# TC364_MainBoard_Power_V1_3.net
KiCad netlist of a schematic drawn in Altium Designer
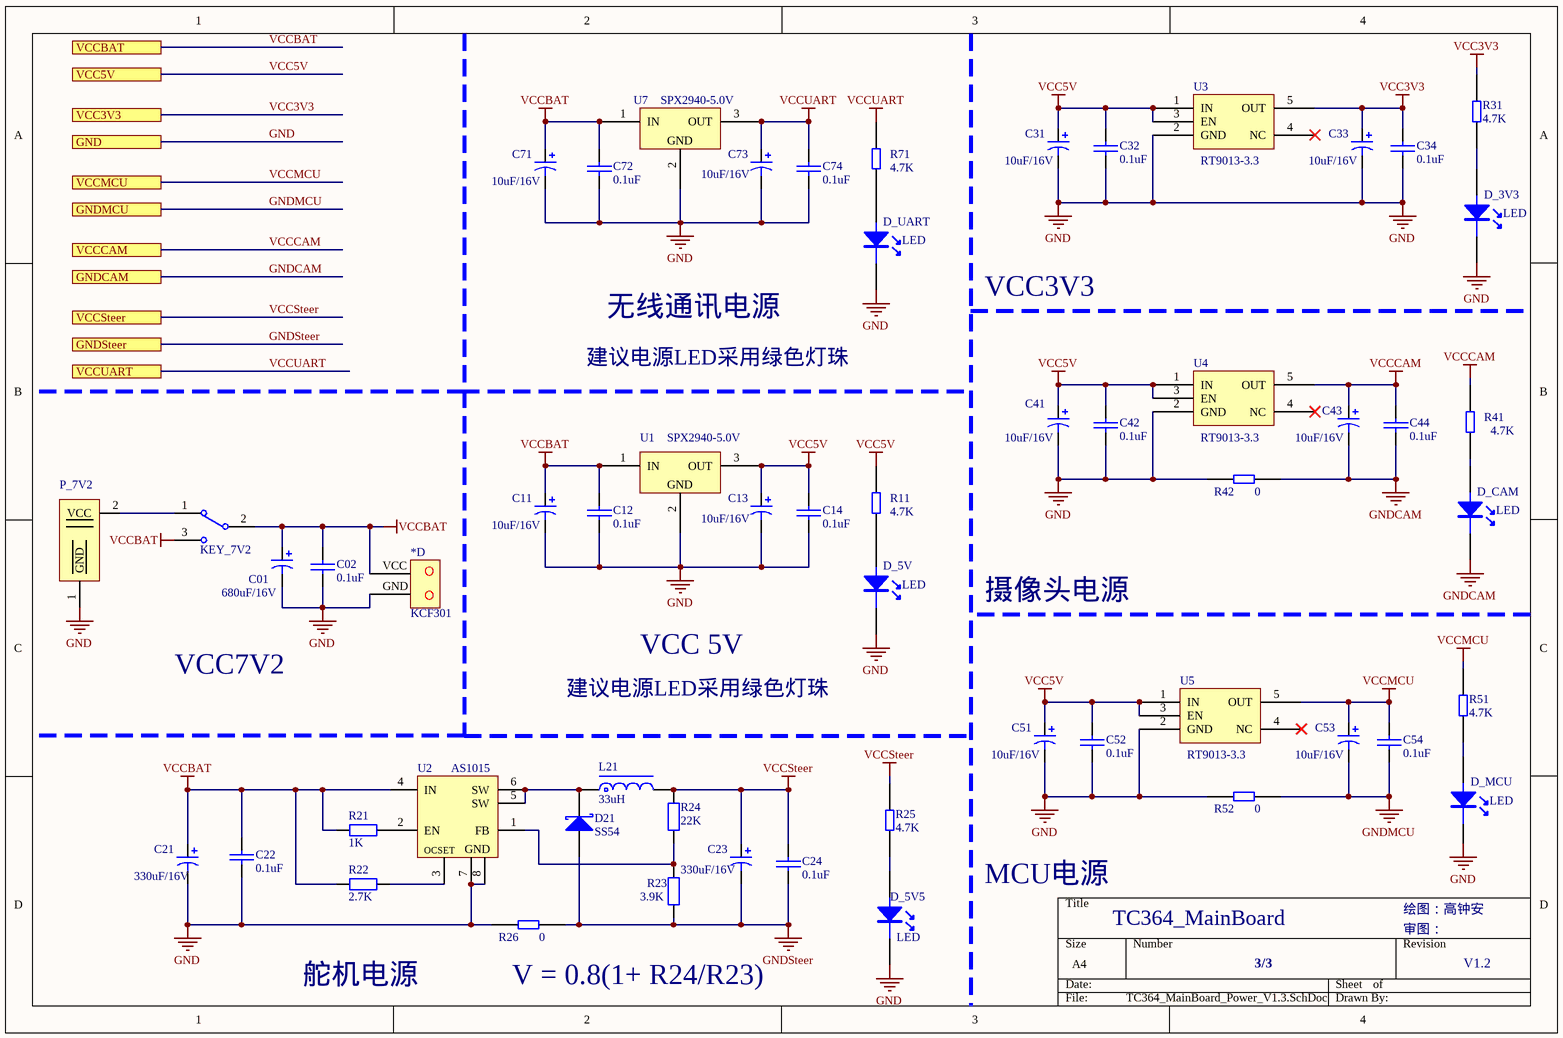
[diagram p0: TC364_MainBoard_Power_V1.3.SchDoc]

(export (version "E")
  (design (tool "Eeschema 10.0.6"))
  (components
    (comp (ref "*") (value "KCF301") (footprint "KF301-2P") (libsource (lib "BaseLib_SCH") (part "KCF301")))
    (comp (ref "C01")
      (value "680uF/16V")
      (footprint "CAP 3.5*8*11.5 - GD")
      (description "Polarized Capacitor (Radial)")
      (fields (field (name "PUBLISHER") "Altium Limited"))
      (libsource (lib "Miscellaneous Devices") (part "Cap Pol1"))
    )
    (comp (ref "C02")
      (value "0.1uF")
      (footprint "0805C")
      (description "Capacitor")
      (libsource (lib "Protel99Lib_SCH") (part "CAP"))
    )
    (comp (ref "C11")
      (value "10uF/16V")
      (footprint "CASE-A_3216")
      (description "Polarized Capacitor (Radial)")
      (fields (field (name "PUBLISHER") "Altium Limited"))
      (libsource (lib "Miscellaneous Devices") (part "Cap Pol1"))
    )
    (comp (ref "C12")
      (value "0.1uF")
      (footprint "0805C")
      (description "Capacitor")
      (libsource (lib "Protel99Lib_SCH") (part "CAP"))
    )
    (comp (ref "C13")
      (value "10uF/16V")
      (footprint "CASE-A_3216")
      (description "Polarized Capacitor (Radial)")
      (fields (field (name "PUBLISHER") "Altium Limited"))
      (libsource (lib "Miscellaneous Devices") (part "Cap Pol1"))
    )
    (comp (ref "C14")
      (value "0.1uF")
      (footprint "0805C")
      (description "Capacitor")
      (libsource (lib "Protel99Lib_SCH") (part "CAP"))
    )
    (comp (ref "C21")
      (value "330uF/16V")
      (footprint "CAP 2.5*6.3*11.2 - BK")
      (description "Polarized Capacitor (Radial)")
      (fields (field (name "PUBLISHER") "Altium Limited"))
      (libsource (lib "Miscellaneous Devices") (part "Cap Pol1"))
    )
    (comp (ref "C22")
      (value "0.1uF")
      (footprint "0805C")
      (description "Capacitor")
      (libsource (lib "Protel99Lib_SCH") (part "CAP"))
    )
    (comp (ref "C23")
      (value "330uF/16V")
      (footprint "CAP 2.5*6.3*11.2 - BK")
      (description "Polarized Capacitor (Radial)")
      (fields (field (name "PUBLISHER") "Altium Limited"))
      (libsource (lib "Miscellaneous Devices") (part "Cap Pol1"))
    )
    (comp (ref "C24")
      (value "0.1uF")
      (footprint "0805C")
      (description "Capacitor")
      (libsource (lib "Protel99Lib_SCH") (part "CAP"))
    )
    (comp (ref "C31")
      (value "10uF/16V")
      (footprint "CASE-A_3216")
      (description "Polarized Capacitor (Radial)")
      (fields (field (name "PUBLISHER") "Altium Limited"))
      (libsource (lib "Miscellaneous Devices") (part "Cap Pol1"))
    )
    (comp (ref "C32")
      (value "0.1uF")
      (footprint "0805C")
      (description "Capacitor")
      (libsource (lib "Protel99Lib_SCH") (part "CAP"))
    )
    (comp (ref "C33")
      (value "10uF/16V")
      (footprint "CASE-A_3216")
      (description "Polarized Capacitor (Radial)")
      (fields (field (name "PUBLISHER") "Altium Limited"))
      (libsource (lib "Miscellaneous Devices") (part "Cap Pol1"))
    )
    (comp (ref "C34")
      (value "0.1uF")
      (footprint "0805C")
      (description "Capacitor")
      (libsource (lib "Protel99Lib_SCH") (part "CAP"))
    )
    (comp (ref "C41")
      (value "10uF/16V")
      (footprint "CASE-A_3216")
      (description "Polarized Capacitor (Radial)")
      (fields (field (name "PUBLISHER") "Altium Limited"))
      (libsource (lib "Miscellaneous Devices") (part "Cap Pol1"))
    )
    (comp (ref "C42")
      (value "0.1uF")
      (footprint "0805C")
      (description "Capacitor")
      (libsource (lib "Protel99Lib_SCH") (part "CAP"))
    )
    (comp (ref "C43")
      (value "10uF/16V")
      (footprint "CASE-A_3216")
      (description "Polarized Capacitor (Radial)")
      (fields (field (name "PUBLISHER") "Altium Limited"))
      (libsource (lib "Miscellaneous Devices") (part "Cap Pol1"))
    )
    (comp (ref "C44")
      (value "0.1uF")
      (footprint "0805C")
      (description "Capacitor")
      (libsource (lib "Protel99Lib_SCH") (part "CAP"))
    )
    (comp (ref "C51")
      (value "10uF/16V")
      (footprint "CASE-A_3216")
      (description "Polarized Capacitor (Radial)")
      (fields (field (name "PUBLISHER") "Altium Limited"))
      (libsource (lib "Miscellaneous Devices") (part "Cap Pol1"))
    )
    (comp (ref "C52")
      (value "0.1uF")
      (footprint "0805C")
      (description "Capacitor")
      (libsource (lib "Protel99Lib_SCH") (part "CAP"))
    )
    (comp (ref "C53")
      (value "10uF/16V")
      (footprint "CASE-A_3216")
      (description "Polarized Capacitor (Radial)")
      (fields (field (name "PUBLISHER") "Altium Limited"))
      (libsource (lib "Miscellaneous Devices") (part "Cap Pol1"))
    )
    (comp (ref "C54")
      (value "0.1uF")
      (footprint "0805C")
      (description "Capacitor")
      (libsource (lib "Protel99Lib_SCH") (part "CAP"))
    )
    (comp (ref "C71")
      (value "10uF/16V")
      (footprint "CASE-A_3216")
      (description "Polarized Capacitor (Radial)")
      (fields (field (name "PUBLISHER") "Altium Limited"))
      (libsource (lib "Miscellaneous Devices") (part "Cap Pol1"))
    )
    (comp (ref "C72")
      (value "0.1uF")
      (footprint "0805C")
      (description "Capacitor")
      (libsource (lib "Protel99Lib_SCH") (part "CAP"))
    )
    (comp (ref "C73")
      (value "10uF/16V")
      (footprint "CASE-A_3216")
      (description "Polarized Capacitor (Radial)")
      (fields (field (name "PUBLISHER") "Altium Limited"))
      (libsource (lib "Miscellaneous Devices") (part "Cap Pol1"))
    )
    (comp (ref "C74")
      (value "0.1uF")
      (footprint "0805C")
      (description "Capacitor")
      (libsource (lib "Protel99Lib_SCH") (part "CAP"))
    )
    (comp (ref "D21")
      (value "SS54")
      (footprint "SMA")
      (description "肖特基二极管")
      (libsource (lib "0.2 -  二极管-整流桥") (part "SS34"))
    )
    (comp (ref "D_3V3")
      (value "LED")
      (footprint "0805_LED_S1")
      (description "发光二极管")
      (libsource (lib "jianing") (part "LED"))
    )
    (comp (ref "D_5V")
      (value "LED")
      (footprint "0805_LED_S1")
      (description "发光二极管")
      (libsource (lib "jianing") (part "LED"))
    )
    (comp (ref "D_5V5")
      (value "LED")
      (footprint "0805_LED_S1")
      (description "发光二极管")
      (libsource (lib "jianing") (part "LED"))
    )
    (comp (ref "D_CAM")
      (value "LED")
      (footprint "0805_LED_S1")
      (description "发光二极管")
      (libsource (lib "jianing") (part "LED"))
    )
    (comp (ref "D_MCU")
      (value "LED")
      (footprint "0805_LED_S1")
      (description "发光二极管")
      (libsource (lib "jianing") (part "LED"))
    )
    (comp (ref "D_UART")
      (value "LED")
      (footprint "0805_LED_S1")
      (description "发光二极管")
      (libsource (lib "jianing") (part "LED"))
    )
    (comp (ref "KEY_7V2")
      (value "SS-12F23")
      (footprint "KEY_7V2")
      (description "1路波动开关")
      (fields (field (name "版权归属") "封装库来自淘宝 ID：黄晶宝石"))
      (libsource (lib "0.7 - 常用按键-开关") (part "SSW-1P"))
    )
    (comp (ref "L21")
      (value "33uH")
      (footprint "7*7 L")
      (description "功率屏蔽电感")
      (fields (field (name "版权归属") "封装库来自淘宝 ID：黄晶宝石"))
      (libsource (lib "0.1 - 电阻-电容-电感") (part "L-CDRH"))
    )
    (comp (ref "P_7V2")
      (value "T_Type_Adapter")
      (footprint "T_Type_Adapter")
      (libsource (lib "Schlib1") (part "T_Type_Adapter"))
    )
    (comp (ref "R11") (value "4.7K") (footprint "0805R") (libsource (lib "BaseLib_SCH") (part "RES")))
    (comp (ref "R21")
      (value "1K")
      (footprint "0805R")
      (description "贴片电阻")
      (fields (field (name "版权归属") "源创客"))
      (libsource (lib "jianing") (part "RES"))
    )
    (comp (ref "R22")
      (value "2.7K")
      (footprint "0805R")
      (description "贴片电阻")
      (fields (field (name "版权归属") "源创客"))
      (libsource (lib "jianing") (part "RES"))
    )
    (comp (ref "R23")
      (value "3.9K")
      (footprint "0805R")
      (description "贴片电阻")
      (fields (field (name "版权归属") "源创客"))
      (libsource (lib "jianing") (part "RES"))
    )
    (comp (ref "R24")
      (value "22K")
      (footprint "0805R")
      (description "贴片电阻")
      (fields (field (name "版权归属") "源创客"))
      (libsource (lib "jianing") (part "RES"))
    )
    (comp (ref "R25") (value "4.7K") (footprint "0805R") (libsource (lib "BaseLib_SCH") (part "RES")))
    (comp (ref "R26") (value "0") (footprint "0805R") (libsource (lib "BaseLib_SCH") (part "RES")))
    (comp (ref "R31") (value "4.7K") (footprint "0805R") (libsource (lib "BaseLib_SCH") (part "RES")))
    (comp (ref "R41") (value "4.7K") (footprint "0805R") (libsource (lib "BaseLib_SCH") (part "RES")))
    (comp (ref "R42") (value "0") (footprint "0805R") (libsource (lib "BaseLib_SCH") (part "RES")))
    (comp (ref "R51") (value "4.7K") (footprint "0805R") (libsource (lib "BaseLib_SCH") (part "RES")))
    (comp (ref "R52") (value "0") (footprint "0805R") (libsource (lib "BaseLib_SCH") (part "RES")))
    (comp (ref "R71") (value "4.7K") (footprint "0805R") (libsource (lib "BaseLib_SCH") (part "RES")))
    (comp (ref "U1")
      (value "SPX2940-5.0V")
      (footprint "TO-220(TO-220-3)")
      (description "5V稳压芯片")
      (fields (field (name "版权归属") "封装库来自淘宝 ID：黄晶宝石"))
      (libsource (lib "1.1 - 电源类芯片") (part "LM2940"))
    )
    (comp (ref "U2")
      (value "AS1015")
      (footprint "SOP-8_150mil")
      (description "可调升压芯片")
      (libsource (lib "1.0 - 常见芯片") (part "AS1015"))
    )
    (comp (ref "U3")
      (value "RT9013-3.3")
      (footprint "SOT-23-5")
      (libsource (lib "jianing") (part "RT9013-3.3"))
    )
    (comp (ref "U4")
      (value "RT9013-3.3")
      (footprint "SOT-23-5")
      (libsource (lib "jianing") (part "RT9013-3.3"))
    )
    (comp (ref "U5")
      (value "RT9013-3.3")
      (footprint "SOT-23-5")
      (libsource (lib "jianing") (part "RT9013-3.3"))
    )
    (comp (ref "U7")
      (value "SPX2940-5.0V")
      (footprint "TO-220(TO-220-3)")
      (description "5V稳压芯片")
      (fields (field (name "版权归属") "封装库来自淘宝 ID：黄晶宝石"))
      (libsource (lib "1.1 - 电源类芯片") (part "LM2940"))
    )
  )
  (nets
    (net (code "1") (name "GND") (class "Default")
      (node (ref "C01") (pin "2") (pinfunction "2_2") (pintype "passive"))
      (node (ref "C02") (pin "2") (pinfunction "2_2") (pintype "passive"))
      (node (ref "C11") (pin "2") (pinfunction "2_2") (pintype "passive"))
      (node (ref "C12") (pin "2") (pinfunction "2_2") (pintype "passive"))
      (node (ref "C13") (pin "2") (pinfunction "2_2") (pintype "passive"))
      (node (ref "C14") (pin "2") (pinfunction "2_2") (pintype "passive"))
      (node (ref "C21") (pin "2") (pinfunction "2_2") (pintype "passive"))
      (node (ref "C22") (pin "2") (pinfunction "2_2") (pintype "passive"))
      (node (ref "C31") (pin "2") (pinfunction "2_2") (pintype "passive"))
      (node (ref "C32") (pin "2") (pinfunction "2_2") (pintype "passive"))
      (node (ref "C33") (pin "2") (pinfunction "2_2") (pintype "passive"))
      (node (ref "C34") (pin "2") (pinfunction "2_2") (pintype "passive"))
      (node (ref "C41") (pin "2") (pinfunction "2_2") (pintype "passive"))
      (node (ref "C42") (pin "2") (pinfunction "2_2") (pintype "passive"))
      (node (ref "C51") (pin "2") (pinfunction "2_2") (pintype "passive"))
      (node (ref "C52") (pin "2") (pinfunction "2_2") (pintype "passive"))
      (node (ref "C71") (pin "2") (pinfunction "2_2") (pintype "passive"))
      (node (ref "C72") (pin "2") (pinfunction "2_2") (pintype "passive"))
      (node (ref "C73") (pin "2") (pinfunction "2_2") (pintype "passive"))
      (node (ref "C74") (pin "2") (pinfunction "2_2") (pintype "passive"))
      (node (ref "D_3V3") (pin "K") (pinfunction "2_K") (pintype "passive"))
      (node (ref "D_5V") (pin "K") (pinfunction "2_K") (pintype "passive"))
      (node (ref "D_5V5") (pin "K") (pinfunction "2_K") (pintype "passive"))
      (node (ref "D_UART") (pin "K") (pinfunction "2_K") (pintype "passive"))
      (node (ref "P_7V2") (pin "1") (pinfunction "GND_1") (pintype "passive"))
      (node (ref "R26") (pin "2") (pinfunction "2_2") (pintype "passive"))
      (node (ref "R42") (pin "2") (pinfunction "2_2") (pintype "passive"))
      (node (ref "R52") (pin "2") (pinfunction "2_2") (pintype "passive"))
      (node (ref "U1") (pin "2") (pinfunction "GND_2") (pintype "power_in"))
      (node (ref "U2") (pin "7") (pinfunction "GND_7") (pintype "power_in"))
      (node (ref "U2") (pin "8") (pinfunction "GND_8") (pintype "power_in"))
      (node (ref "U3") (pin "2") (pinfunction "GND_2") (pintype "passive"))
      (node (ref "U4") (pin "2") (pinfunction "GND_2") (pintype "passive"))
      (node (ref "U5") (pin "2") (pinfunction "GND_2") (pintype "passive"))
      (node (ref "U7") (pin "2") (pinfunction "GND_2") (pintype "power_in"))
    )
    (net (code "2") (name "GNDCAM") (class "Default")
      (node (ref "C43") (pin "2") (pinfunction "2_2") (pintype "passive"))
      (node (ref "C44") (pin "2") (pinfunction "2_2") (pintype "passive"))
      (node (ref "D_CAM") (pin "K") (pinfunction "2_K") (pintype "passive"))
      (node (ref "R42") (pin "1") (pinfunction "1_1") (pintype "passive"))
    )
    (net (code "3") (name "GNDMCU") (class "Default")
      (node (ref "C53") (pin "2") (pinfunction "2_2") (pintype "passive"))
      (node (ref "C54") (pin "2") (pinfunction "2_2") (pintype "passive"))
      (node (ref "R52") (pin "1") (pinfunction "1_1") (pintype "passive"))
    )
    (net (code "4") (name "GNDSteer") (class "Default")
      (node (ref "C23") (pin "2") (pinfunction "2_2") (pintype "passive"))
      (node (ref "C24") (pin "2") (pinfunction "2_2") (pintype "passive"))
      (node (ref "D21") (pin "1") (pinfunction "A_1") (pintype "passive"))
      (node (ref "R23") (pin "2") (pinfunction "2_2") (pintype "passive"))
      (node (ref "R26") (pin "1") (pinfunction "1_1") (pintype "passive"))
    )
    (net (code "5") (name "Net-(D21-K)") (class "Default")
      (node (ref "D21") (pin "2") (pinfunction "K_2") (pintype "passive"))
      (node (ref "L21") (pin "1") (pinfunction "1_1") (pintype "passive"))
      (node (ref "U2") (pin "5") (pinfunction "SW_5") (pintype "power_in"))
      (node (ref "U2") (pin "6") (pinfunction "SW_6") (pintype "power_in"))
    )
    (net (code "6") (name "Net-(D_3V3-1)") (class "Default")
      (node (ref "D_3V3") (pin "A") (pinfunction "1_A") (pintype "passive"))
      (node (ref "R31") (pin "2") (pinfunction "2_2") (pintype "passive"))
    )
    (net (code "7") (name "Net-(D_5V-1)") (class "Default")
      (node (ref "D_5V") (pin "A") (pinfunction "1_A") (pintype "passive"))
      (node (ref "R11") (pin "2") (pinfunction "2_2") (pintype "passive"))
    )
    (net (code "8") (name "Net-(D_5V5-1)") (class "Default")
      (node (ref "D_5V5") (pin "A") (pinfunction "1_A") (pintype "passive"))
      (node (ref "R25") (pin "2") (pinfunction "2_2") (pintype "passive"))
    )
    (net (code "9") (name "Net-(D_CAM-1)") (class "Default")
      (node (ref "D_CAM") (pin "A") (pinfunction "1_A") (pintype "passive"))
      (node (ref "R41") (pin "2") (pinfunction "2_2") (pintype "passive"))
    )
    (net (code "10") (name "Net-(D_MCU-1)") (class "Default")
      (node (ref "D_MCU") (pin "A") (pinfunction "1_A") (pintype "passive"))
      (node (ref "R51") (pin "2") (pinfunction "2_2") (pintype "passive"))
    )
    (net (code "11") (name "Net-(D_UART-1)") (class "Default")
      (node (ref "D_UART") (pin "A") (pinfunction "1_A") (pintype "passive"))
      (node (ref "R71") (pin "2") (pinfunction "2_2") (pintype "passive"))
    )
    (net (code "12") (name "Net-(P_7V2-VCC)") (class "Default")
      (node (ref "KEY_7V2") (pin "1") (pinfunction "1_1") (pintype "passive"))
      (node (ref "P_7V2") (pin "2") (pinfunction "VCC_2") (pintype "passive"))
    )
    (net (code "13") (name "Net-(U2-EN)") (class "Default")
      (node (ref "R21") (pin "1") (pinfunction "1_1") (pintype "passive"))
      (node (ref "U2") (pin "2") (pinfunction "EN_2") (pintype "power_in"))
    )
    (net (code "14") (name "Net-(U2-FB)") (class "Default")
      (node (ref "R23") (pin "1") (pinfunction "1_1") (pintype "passive"))
      (node (ref "R24") (pin "2") (pinfunction "2_2") (pintype "passive"))
      (node (ref "U2") (pin "1") (pinfunction "FB_1") (pintype "power_in"))
    )
    (net (code "15") (name "Net-(U2-OCSET)") (class "Default")
      (node (ref "R22") (pin "1") (pinfunction "1_1") (pintype "passive"))
      (node (ref "U2") (pin "3") (pinfunction "OCSET_3") (pintype "power_in"))
    )
    (net (code "16") (name "VCC3V3") (class "Default")
      (node (ref "C33") (pin "1") (pinfunction "1_1") (pintype "passive"))
      (node (ref "C34") (pin "1") (pinfunction "1_1") (pintype "passive"))
      (node (ref "R31") (pin "1") (pinfunction "1_1") (pintype "passive"))
      (node (ref "U3") (pin "5") (pinfunction "OUT_5") (pintype "passive"))
    )
    (net (code "17") (name "VCC5V") (class "Default")
      (node (ref "C13") (pin "1") (pinfunction "1_1") (pintype "passive"))
      (node (ref "C14") (pin "1") (pinfunction "1_1") (pintype "passive"))
      (node (ref "C31") (pin "1") (pinfunction "1_1") (pintype "passive"))
      (node (ref "C32") (pin "1") (pinfunction "1_1") (pintype "passive"))
      (node (ref "C41") (pin "1") (pinfunction "1_1") (pintype "passive"))
      (node (ref "C42") (pin "1") (pinfunction "1_1") (pintype "passive"))
      (node (ref "C51") (pin "1") (pinfunction "1_1") (pintype "passive"))
      (node (ref "C52") (pin "1") (pinfunction "1_1") (pintype "passive"))
      (node (ref "R11") (pin "1") (pinfunction "1_1") (pintype "passive"))
      (node (ref "U1") (pin "3") (pinfunction "OUT_3") (pintype "power_in"))
      (node (ref "U3") (pin "1") (pinfunction "IN_1") (pintype "passive"))
      (node (ref "U3") (pin "3") (pinfunction "EN_3") (pintype "passive"))
      (node (ref "U4") (pin "1") (pinfunction "IN_1") (pintype "passive"))
      (node (ref "U4") (pin "3") (pinfunction "EN_3") (pintype "passive"))
      (node (ref "U5") (pin "1") (pinfunction "IN_1") (pintype "passive"))
      (node (ref "U5") (pin "3") (pinfunction "EN_3") (pintype "passive"))
    )
    (net (code "18") (name "VCCBAT") (class "Default")
      (node (ref "C01") (pin "1") (pinfunction "1_1") (pintype "passive"))
      (node (ref "C02") (pin "1") (pinfunction "1_1") (pintype "passive"))
      (node (ref "C11") (pin "1") (pinfunction "1_1") (pintype "passive"))
      (node (ref "C12") (pin "1") (pinfunction "1_1") (pintype "passive"))
      (node (ref "C21") (pin "1") (pinfunction "1_1") (pintype "passive"))
      (node (ref "C22") (pin "1") (pinfunction "1_1") (pintype "passive"))
      (node (ref "C71") (pin "1") (pinfunction "1_1") (pintype "passive"))
      (node (ref "C72") (pin "1") (pinfunction "1_1") (pintype "passive"))
      (node (ref "KEY_7V2") (pin "2") (pinfunction "2_2") (pintype "passive"))
      (node (ref "KEY_7V2") (pin "3") (pinfunction "3_3") (pintype "passive"))
      (node (ref "R21") (pin "2") (pinfunction "2_2") (pintype "passive"))
      (node (ref "R22") (pin "2") (pinfunction "2_2") (pintype "passive"))
      (node (ref "U1") (pin "1") (pinfunction "IN_1") (pintype "power_in"))
      (node (ref "U2") (pin "4") (pinfunction "IN_4") (pintype "power_in"))
      (node (ref "U7") (pin "1") (pinfunction "IN_1") (pintype "power_in"))
    )
    (net (code "19") (name "VCCCAM") (class "Default")
      (node (ref "C43") (pin "1") (pinfunction "1_1") (pintype "passive"))
      (node (ref "C44") (pin "1") (pinfunction "1_1") (pintype "passive"))
      (node (ref "R41") (pin "1") (pinfunction "1_1") (pintype "passive"))
      (node (ref "U4") (pin "5") (pinfunction "OUT_5") (pintype "passive"))
    )
    (net (code "20") (name "VCCMCU") (class "Default")
      (node (ref "C53") (pin "1") (pinfunction "1_1") (pintype "passive"))
      (node (ref "C54") (pin "1") (pinfunction "1_1") (pintype "passive"))
      (node (ref "R51") (pin "1") (pinfunction "1_1") (pintype "passive"))
      (node (ref "U5") (pin "5") (pinfunction "OUT_5") (pintype "passive"))
    )
    (net (code "21") (name "VCCSteer") (class "Default")
      (node (ref "C23") (pin "1") (pinfunction "1_1") (pintype "passive"))
      (node (ref "C24") (pin "1") (pinfunction "1_1") (pintype "passive"))
      (node (ref "L21") (pin "2") (pinfunction "2_2") (pintype "passive"))
      (node (ref "R24") (pin "1") (pinfunction "1_1") (pintype "passive"))
      (node (ref "R25") (pin "1") (pinfunction "1_1") (pintype "passive"))
    )
    (net (code "22") (name "VCCUART") (class "Default")
      (node (ref "C73") (pin "1") (pinfunction "1_1") (pintype "passive"))
      (node (ref "C74") (pin "1") (pinfunction "1_1") (pintype "passive"))
      (node (ref "R71") (pin "1") (pinfunction "1_1") (pintype "passive"))
      (node (ref "U7") (pin "3") (pinfunction "OUT_3") (pintype "power_in"))
    )
    (net (code "23") (name "unconnected-(*D-0-PadVCC)") (class "Default")
      (node (ref "*") (pin "VCC") (pinfunction "0_VCC") (pintype "passive"))
    )
    (net (code "24") (name "unconnected-(*D-1-PadGND)") (class "Default")
      (node (ref "*") (pin "GND") (pinfunction "1_GND") (pintype "passive"))
    )
    (net (code "25") (name "unconnected-(D_MCU-2-PadK)") (class "Default")
      (node (ref "D_MCU") (pin "K") (pinfunction "2_K") (pintype "passive"))
    )
    (net (code "26") (name "unconnected-(U3-NC-Pad4)") (class "Default")
      (node (ref "U3") (pin "4") (pinfunction "NC_4") (pintype "passive+no_connect"))
    )
    (net (code "27") (name "unconnected-(U4-NC-Pad4)") (class "Default")
      (node (ref "U4") (pin "4") (pinfunction "NC_4") (pintype "passive+no_connect"))
    )
    (net (code "28") (name "unconnected-(U5-NC-Pad4)") (class "Default")
      (node (ref "U5") (pin "4") (pinfunction "NC_4") (pintype "passive+no_connect"))
    )
  )
)
